# ElectronBoardMKI.net
KiCad netlist of a schematic drawn in EAGLE
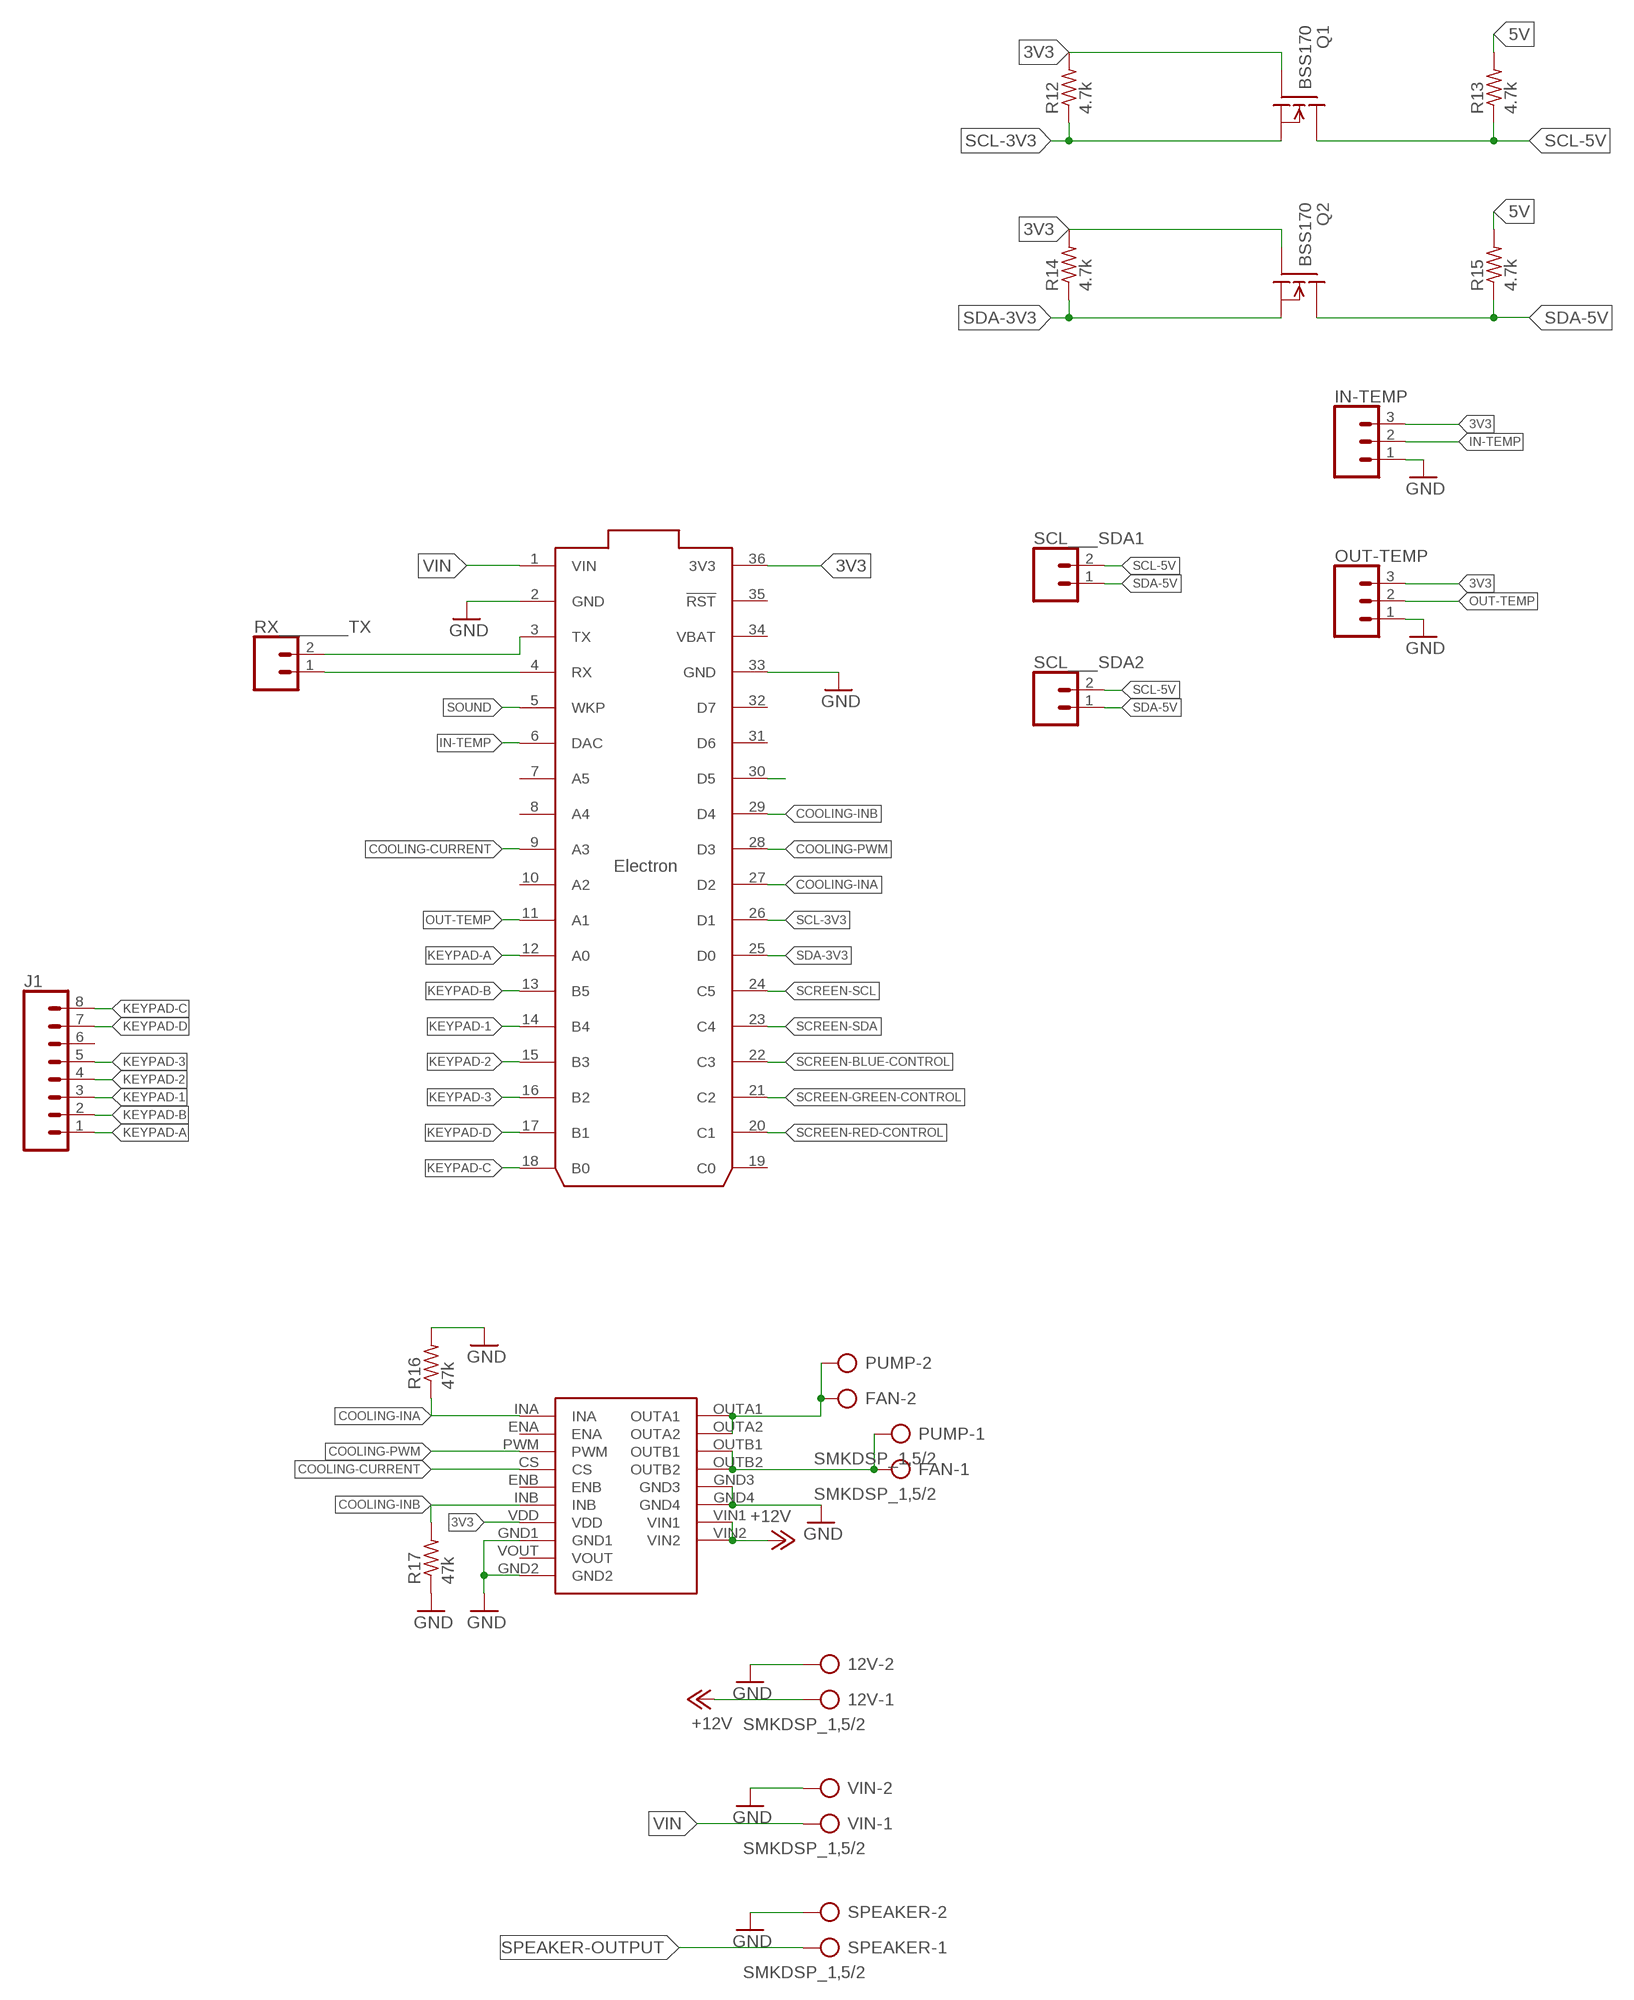
[diagram p0: schematic, sheet 1, part 1 of 2]
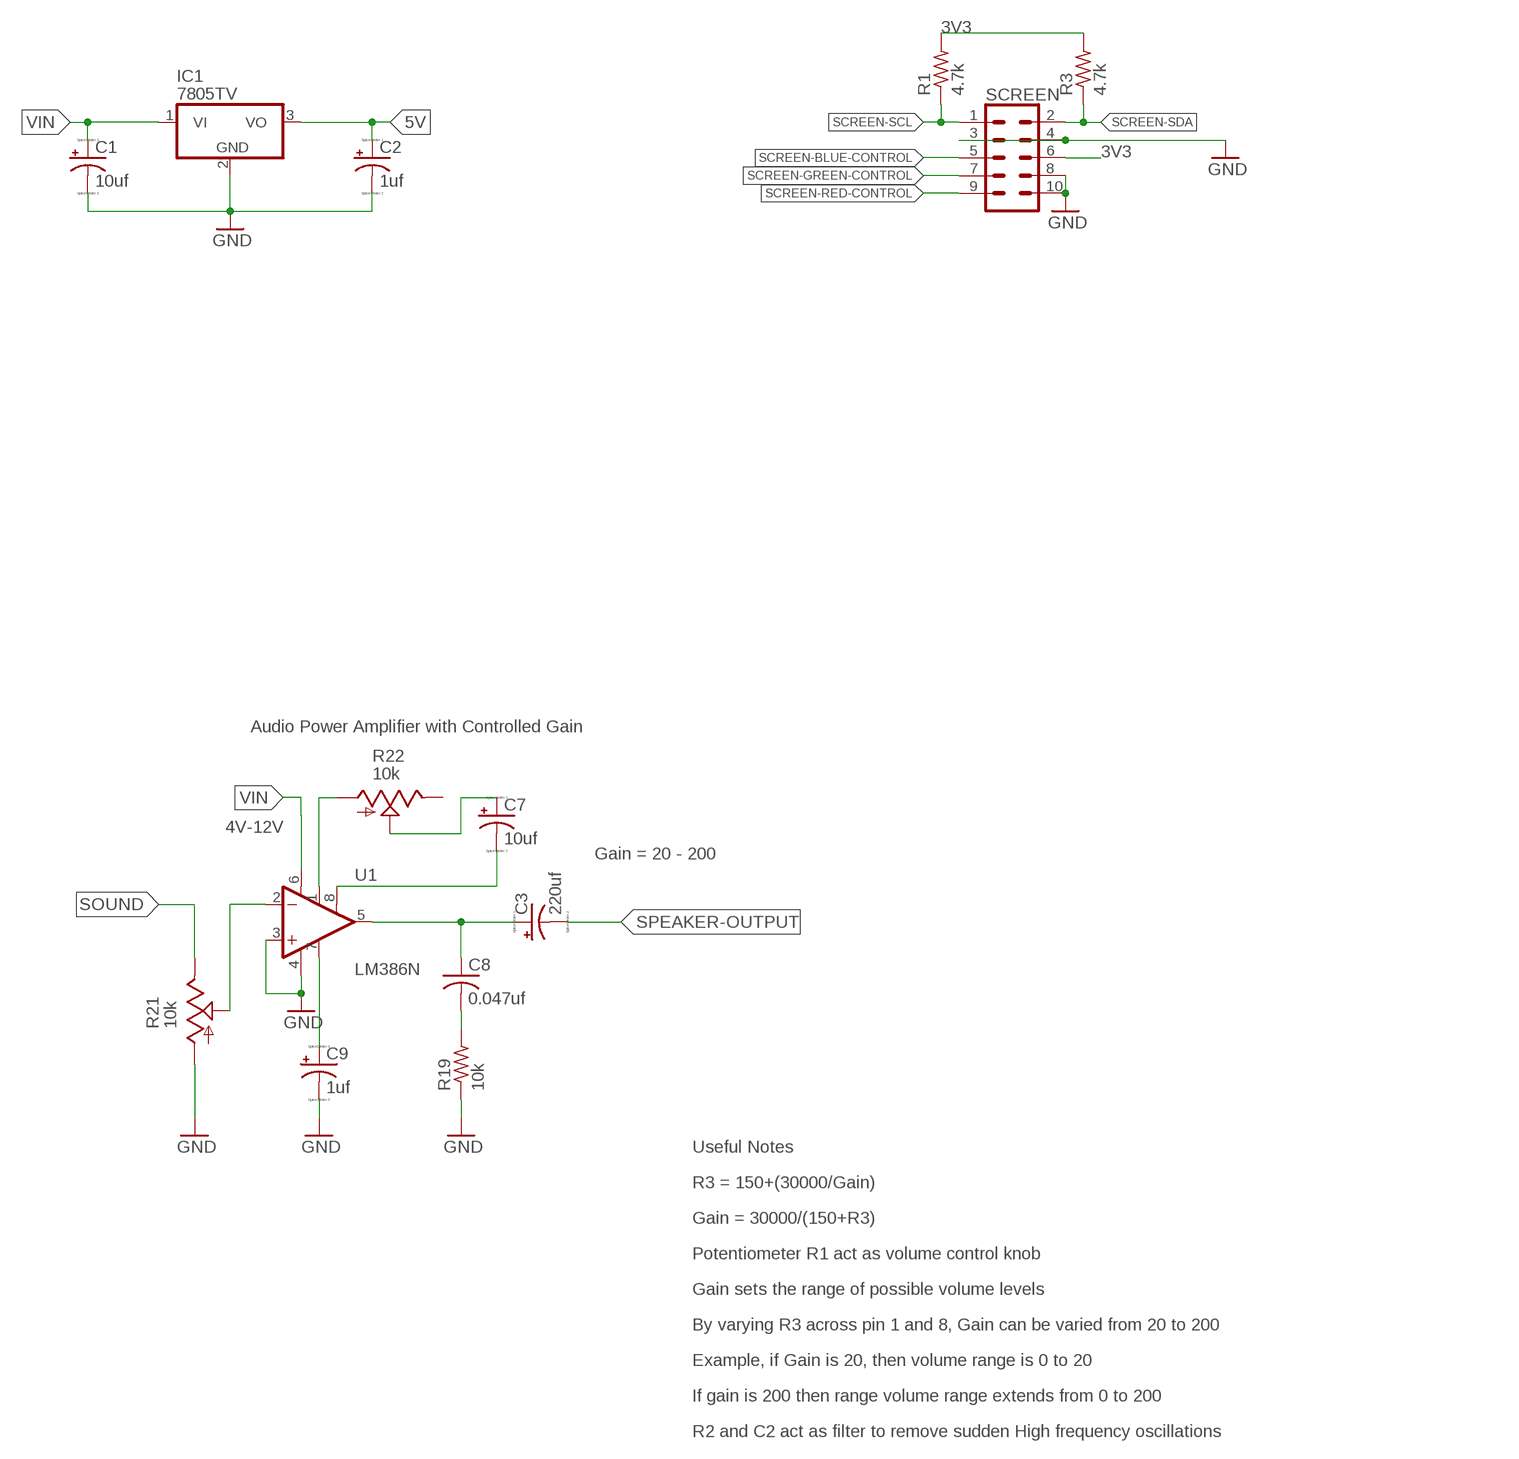
[diagram p1: schematic, sheet 1, part 2 of 2]

(export (version "E")
  (design (tool "Eeschema 10.0.6"))
  (components
    (comp (ref "12V")
      (value "SMKDSP_1,5/2")
      (footprint "eagle-import:SMKDSP_1,5_2")
      (fields (field (name "MF") "FARNELL") (field (name "MPN") "1733570"))
      (libsource (lib "eagle-import") (part "SMKDSP_1,5/2"))
    )
    (comp (ref "C1")
      (value "10uf")
      (footprint "eagle-import:E5-8,5")
      (libsource (lib "eagle-import") (part "CPOL-USE5-8.5"))
    )
    (comp (ref "C2")
      (value "1uf")
      (footprint "eagle-import:E5-8,5")
      (libsource (lib "eagle-import") (part "CPOL-USE5-8.5"))
    )
    (comp (ref "C3")
      (value "220uf")
      (footprint "eagle-import:E5-8,5")
      (libsource (lib "eagle-import") (part "CPOL-USE5-8.5"))
    )
    (comp (ref "C7")
      (value "10uf")
      (footprint "eagle-import:E5-8,5")
      (libsource (lib "eagle-import") (part "CPOL-USE5-8.5"))
    )
    (comp (ref "C8")
      (value "0.047uf")
      (footprint "eagle-import:C050-035X075")
      (libsource (lib "eagle-import") (part "C-US050-035X075"))
    )
    (comp (ref "C9")
      (value "1uf")
      (footprint "eagle-import:E5-8,5")
      (libsource (lib "eagle-import") (part "CPOL-USE5-8.5"))
    )
    (comp (ref "FAN")
      (value "SMKDSP_1,5/2")
      (footprint "eagle-import:SMKDSP_1,5_2")
      (fields (field (name "MF") "FARNELL") (field (name "MPN") "1733570"))
      (libsource (lib "eagle-import") (part "SMKDSP_1,5/2"))
    )
    (comp (ref "IC1")
      (value "7805TV")
      (footprint "eagle-import:TO220V")
      (libsource (lib "eagle-import") (part "78TV05"))
    )
    (comp (ref "IN-TEMP")
      (value "CONN_03LOCK_LONGPADS")
      (footprint "eagle-import:1X03_LOCK_LONGPADS")
      (libsource (lib "eagle-import") (part "CONN_03LOCK_LONGPADS"))
    )
    (comp (ref "J1")
      (value "CONN_08LOCK_LONGPADS")
      (footprint "eagle-import:1X08_LOCK_LONGPADS")
      (libsource (lib "eagle-import") (part "CONN_08LOCK_LONGPADS"))
    )
    (comp (ref "OUT-TEMP")
      (value "CONN_03LOCK_LONGPADS")
      (footprint "eagle-import:1X03_LOCK_LONGPADS")
      (libsource (lib "eagle-import") (part "CONN_03LOCK_LONGPADS"))
    )
    (comp (ref "PUMP")
      (value "SMKDSP_1,5/2")
      (footprint "eagle-import:SMKDSP_1,5_2")
      (fields (field (name "MF") "FARNELL") (field (name "MPN") "1733570"))
      (libsource (lib "eagle-import") (part "SMKDSP_1,5/2"))
    )
    (comp (ref "Q1")
      (value "BSS170")
      (footprint "eagle-import:TO92")
      (libsource (lib "eagle-import") (part "BSS101"))
    )
    (comp (ref "Q2")
      (value "BSS170")
      (footprint "eagle-import:TO92")
      (libsource (lib "eagle-import") (part "BSS101"))
    )
    (comp (ref "R1")
      (value "4.7k")
      (footprint "eagle-import:0207_12")
      (libsource (lib "eagle-import") (part "R-US_0207/12"))
    )
    (comp (ref "R3")
      (value "4.7k")
      (footprint "eagle-import:0207_12")
      (libsource (lib "eagle-import") (part "R-US_0207/12"))
    )
    (comp (ref "R12")
      (value "4.7k")
      (footprint "eagle-import:0207_12")
      (libsource (lib "eagle-import") (part "R-US_0207/12"))
    )
    (comp (ref "R13")
      (value "4.7k")
      (footprint "eagle-import:0207_12")
      (libsource (lib "eagle-import") (part "R-US_0207/12"))
    )
    (comp (ref "R14")
      (value "4.7k")
      (footprint "eagle-import:0207_12")
      (libsource (lib "eagle-import") (part "R-US_0207/12"))
    )
    (comp (ref "R15")
      (value "4.7k")
      (footprint "eagle-import:0207_12")
      (libsource (lib "eagle-import") (part "R-US_0207/12"))
    )
    (comp (ref "R16")
      (value "47k")
      (footprint "eagle-import:0207_12")
      (libsource (lib "eagle-import") (part "R-US_0207/12"))
    )
    (comp (ref "R17")
      (value "47k")
      (footprint "eagle-import:0207_12")
      (libsource (lib "eagle-import") (part "R-US_0207/12"))
    )
    (comp (ref "R19")
      (value "10k")
      (footprint "eagle-import:0207_12")
      (libsource (lib "eagle-import") (part "R-US_0207/12"))
    )
    (comp (ref "R21")
      (value "10k")
      (footprint "eagle-import:CT6")
      (libsource (lib "eagle-import") (part "TRIM_US-CT6"))
    )
    (comp (ref "R22")
      (value "10k")
      (footprint "eagle-import:CT6")
      (libsource (lib "eagle-import") (part "TRIM_US-CT6"))
    )
    (comp (ref "RX_______TX")
      (value "CONN_02LOCK_LONGPADS")
      (footprint "eagle-import:1X02_LOCK_LONGPADS")
      (libsource (lib "eagle-import") (part "CONN_02LOCK_LONGPADS"))
    )
    (comp (ref "SCL___SDA1")
      (value "CONN_02LOCK_LONGPADS")
      (footprint "eagle-import:1X02_LOCK_LONGPADS")
      (libsource (lib "eagle-import") (part "CONN_02LOCK_LONGPADS"))
    )
    (comp (ref "SCL___SDA2")
      (value "CONN_02LOCK_LONGPADS")
      (footprint "eagle-import:1X02_LOCK_LONGPADS")
      (libsource (lib "eagle-import") (part "CONN_02LOCK_LONGPADS"))
    )
    (comp (ref "SCREEN")
      (value "CONN_05X2SHD")
      (footprint "eagle-import:2X5-SHROUDED")
      (libsource (lib "eagle-import") (part "CONN_05X2SHD"))
    )
    (comp (ref "SPEAKER")
      (value "SMKDSP_1,5/2")
      (footprint "eagle-import:SMKDSP_1,5_2")
      (fields (field (name "MF") "FARNELL") (field (name "MPN") "1733570"))
      (libsource (lib "eagle-import") (part "SMKDSP_1,5/2"))
    )
    (comp (ref "U$1")
      (value "ELECTRON_WITH_HEADERS")
      (footprint "eagle-import:ELECTRON")
      (libsource (lib "eagle-import") (part "ELECTRON_WITH_HEADERS"))
    )
    (comp (ref "U$2")
      (value "VNH5019VNH5019BOARD")
      (footprint "eagle-import:DIP3302W60P254L2400H500Q20B")
      (libsource (lib "eagle-import") (part "VNH5019VNH5019BOARD"))
    )
    (comp (ref "U1")
      (value "LM386N")
      (footprint "eagle-import:DIP08")
      (libsource (lib "eagle-import") (part "LM386"))
    )
    (comp (ref "VIN")
      (value "SMKDSP_1,5/2")
      (footprint "eagle-import:SMKDSP_1,5_2")
      (fields (field (name "MF") "FARNELL") (field (name "MPN") "1733570"))
      (libsource (lib "eagle-import") (part "SMKDSP_1,5/2"))
    )
  )
  (nets
    (net (code "1") (name "+12V") (class "Default")
      (node (ref "12V") (pin "1") (pinfunction "KL_1") (pintype "passive"))
      (node (ref "U$2") (pin "VIN1") (pinfunction "VIN1_VIN1") (pintype "bidirectional"))
      (node (ref "U$2") (pin "VIN2") (pinfunction "VIN2_VIN2") (pintype "bidirectional"))
    )
    (net (code "2") (name "/VBAT") (class "Default")
      (node (ref "U$1") (pin "34") (pinfunction "VBAT_34") (pintype "power_in"))
    )
    (net (code "3") (name "3V3") (class "Default")
      (node (ref "IN-TEMP") (pin "3") (pinfunction "3_3") (pintype "passive"))
      (node (ref "OUT-TEMP") (pin "3") (pinfunction "3_3") (pintype "passive"))
      (node (ref "Q1") (pin "2") (pinfunction "G_2") (pintype "passive"))
      (node (ref "Q2") (pin "2") (pinfunction "G_2") (pintype "passive"))
      (node (ref "R1") (pin "2") (pinfunction "2_2") (pintype "passive"))
      (node (ref "R12") (pin "2") (pinfunction "2_2") (pintype "passive"))
      (node (ref "R14") (pin "2") (pinfunction "2_2") (pintype "passive"))
      (node (ref "R3") (pin "2") (pinfunction "2_2") (pintype "passive"))
      (node (ref "SCREEN") (pin "6") (pinfunction "6_6") (pintype "passive"))
      (node (ref "U$1") (pin "36") (pinfunction "3V3_36") (pintype "power_in"))
      (node (ref "U$2") (pin "VDD") (pinfunction "VDD_VDD") (pintype "bidirectional"))
    )
    (net (code "4") (name "5V") (class "Default")
      (node (ref "C2") (pin "+") (pinfunction "+_+") (pintype "passive"))
      (node (ref "IC1") (pin "3") (pinfunction "VO_3") (pintype "passive"))
      (node (ref "R13") (pin "2") (pinfunction "2_2") (pintype "passive"))
      (node (ref "R15") (pin "2") (pinfunction "2_2") (pintype "passive"))
    )
    (net (code "5") (name "COOLING-CURRENT") (class "Default")
      (node (ref "U$1") (pin "9") (pinfunction "A3_9") (pintype "bidirectional"))
      (node (ref "U$2") (pin "CS") (pinfunction "CS_CS") (pintype "bidirectional"))
    )
    (net (code "6") (name "COOLING-INA") (class "Default")
      (node (ref "R16") (pin "1") (pinfunction "1_1") (pintype "passive"))
      (node (ref "U$1") (pin "27") (pinfunction "D2_27") (pintype "bidirectional"))
      (node (ref "U$2") (pin "INA") (pinfunction "INA_INA") (pintype "bidirectional"))
    )
    (net (code "7") (name "COOLING-INB") (class "Default")
      (node (ref "R17") (pin "2") (pinfunction "2_2") (pintype "passive"))
      (node (ref "U$1") (pin "29") (pinfunction "D4_29") (pintype "bidirectional"))
      (node (ref "U$2") (pin "INB") (pinfunction "INB_INB") (pintype "bidirectional"))
    )
    (net (code "8") (name "COOLING-PWM") (class "Default")
      (node (ref "U$1") (pin "28") (pinfunction "D3_28") (pintype "bidirectional"))
      (node (ref "U$2") (pin "PWM") (pinfunction "PWM_PWM") (pintype "bidirectional"))
    )
    (net (code "9") (name "GND") (class "Default")
      (node (ref "12V") (pin "2") (pinfunction "KL_2") (pintype "passive"))
      (node (ref "C1") (pin "-") (pinfunction "-_-") (pintype "passive"))
      (node (ref "C2") (pin "-") (pinfunction "-_-") (pintype "passive"))
      (node (ref "C9") (pin "-") (pinfunction "-_-") (pintype "passive"))
      (node (ref "IC1") (pin "2") (pinfunction "GND_2") (pintype "passive"))
      (node (ref "IN-TEMP") (pin "1") (pinfunction "1_1") (pintype "passive"))
      (node (ref "OUT-TEMP") (pin "1") (pinfunction "1_1") (pintype "passive"))
      (node (ref "R16") (pin "2") (pinfunction "2_2") (pintype "passive"))
      (node (ref "R17") (pin "1") (pinfunction "1_1") (pintype "passive"))
      (node (ref "R19") (pin "1") (pinfunction "1_1") (pintype "passive"))
      (node (ref "R21") (pin "A") (pinfunction "A_A") (pintype "passive"))
      (node (ref "SCREEN") (pin "10") (pinfunction "10_10") (pintype "passive"))
      (node (ref "SCREEN") (pin "3") (pinfunction "3_3") (pintype "passive"))
      (node (ref "SCREEN") (pin "4") (pinfunction "4_4") (pintype "passive"))
      (node (ref "SCREEN") (pin "8") (pinfunction "8_8") (pintype "passive"))
      (node (ref "SPEAKER") (pin "2") (pinfunction "KL_2") (pintype "passive"))
      (node (ref "U$1") (pin "2") (pinfunction "GND_2") (pintype "power_in"))
      (node (ref "U$1") (pin "33") (pinfunction "GND_33") (pintype "power_in"))
      (node (ref "U$2") (pin "GND1") (pinfunction "GND1_GND1") (pintype "bidirectional"))
      (node (ref "U$2") (pin "GND2") (pinfunction "GND2_GND2") (pintype "bidirectional"))
      (node (ref "U$2") (pin "GND3") (pinfunction "GND3_GND3") (pintype "bidirectional"))
      (node (ref "U$2") (pin "GND4") (pinfunction "GND4_GND4") (pintype "bidirectional"))
      (node (ref "U1") (pin "3") (pinfunction "+IN_3") (pintype "input"))
      (node (ref "U1") (pin "4") (pinfunction "V-_4") (pintype "power_in"))
      (node (ref "VIN") (pin "2") (pinfunction "KL_2") (pintype "passive"))
    )
    (net (code "10") (name "IN-TEMP") (class "Default")
      (node (ref "IN-TEMP") (pin "2") (pinfunction "2_2") (pintype "passive"))
      (node (ref "U$1") (pin "6") (pinfunction "DAC_6") (pintype "bidirectional"))
    )
    (net (code "11") (name "KEYPAD-1") (class "Default")
      (node (ref "J1") (pin "3") (pinfunction "3_3") (pintype "passive"))
      (node (ref "U$1") (pin "14") (pinfunction "B4_14") (pintype "bidirectional"))
    )
    (net (code "12") (name "KEYPAD-2") (class "Default")
      (node (ref "J1") (pin "4") (pinfunction "4_4") (pintype "passive"))
      (node (ref "U$1") (pin "15") (pinfunction "B3_15") (pintype "bidirectional"))
    )
    (net (code "13") (name "KEYPAD-3") (class "Default")
      (node (ref "J1") (pin "5") (pinfunction "5_5") (pintype "passive"))
      (node (ref "U$1") (pin "16") (pinfunction "B2_16") (pintype "bidirectional"))
    )
    (net (code "14") (name "KEYPAD-A") (class "Default")
      (node (ref "J1") (pin "1") (pinfunction "1_1") (pintype "passive"))
      (node (ref "U$1") (pin "12") (pinfunction "A0_12") (pintype "bidirectional"))
    )
    (net (code "15") (name "KEYPAD-B") (class "Default")
      (node (ref "J1") (pin "2") (pinfunction "2_2") (pintype "passive"))
      (node (ref "U$1") (pin "13") (pinfunction "B5_13") (pintype "bidirectional"))
    )
    (net (code "16") (name "KEYPAD-C") (class "Default")
      (node (ref "J1") (pin "8") (pinfunction "8_8") (pintype "passive"))
      (node (ref "U$1") (pin "18") (pinfunction "B0_18") (pintype "bidirectional"))
    )
    (net (code "17") (name "KEYPAD-D") (class "Default")
      (node (ref "J1") (pin "7") (pinfunction "7_7") (pintype "passive"))
      (node (ref "U$1") (pin "17") (pinfunction "B1_17") (pintype "bidirectional"))
    )
    (net (code "18") (name "Net-(C7-Pad+)") (class "Default")
      (node (ref "C7") (pin "+") (pinfunction "+_+") (pintype "passive"))
      (node (ref "R22") (pin "S") (pinfunction "S_S") (pintype "passive"))
    )
    (net (code "19") (name "Net-(C7-Pad-)") (class "Default")
      (node (ref "C7") (pin "-") (pinfunction "-_-") (pintype "passive"))
      (node (ref "U1") (pin "8") (pinfunction "GAIN_8") (pintype "bidirectional"))
    )
    (net (code "20") (name "Net-(C8-Pad2)") (class "Default")
      (node (ref "C8") (pin "2") (pinfunction "2_2") (pintype "passive"))
      (node (ref "R19") (pin "2") (pinfunction "2_2") (pintype "passive"))
    )
    (net (code "21") (name "Net-(FANA-KL)") (class "Default")
      (node (ref "FAN") (pin "1") (pinfunction "KL_1") (pintype "passive"))
      (node (ref "PUMP") (pin "1") (pinfunction "KL_1") (pintype "passive"))
      (node (ref "U$2") (pin "OUTB1") (pinfunction "OUTB1_OUTB1") (pintype "bidirectional"))
      (node (ref "U$2") (pin "OUTB2") (pinfunction "OUTB2_OUTB2") (pintype "bidirectional"))
    )
    (net (code "22") (name "Net-(FANB-KL)") (class "Default")
      (node (ref "FAN") (pin "2") (pinfunction "KL_2") (pintype "passive"))
      (node (ref "PUMP") (pin "2") (pinfunction "KL_2") (pintype "passive"))
      (node (ref "U$2") (pin "OUTA1") (pinfunction "OUTA1_OUTA1") (pintype "bidirectional"))
      (node (ref "U$2") (pin "OUTA2") (pinfunction "OUTA2_OUTA2") (pintype "bidirectional"))
    )
    (net (code "23") (name "Net-(R22-PadA)") (class "Default")
      (node (ref "R22") (pin "A") (pinfunction "A_A") (pintype "passive"))
      (node (ref "U1") (pin "1") (pinfunction "GAIN_1") (pintype "bidirectional"))
    )
    (net (code "24") (name "Net-(U$1-RX)") (class "Default")
      (node (ref "RX_______TX") (pin "1") (pinfunction "1_1") (pintype "passive"))
      (node (ref "U$1") (pin "4") (pinfunction "RX_4") (pintype "bidirectional"))
    )
    (net (code "25") (name "Net-(U$1-TX)") (class "Default")
      (node (ref "RX_______TX") (pin "2") (pinfunction "2_2") (pintype "passive"))
      (node (ref "U$1") (pin "3") (pinfunction "TX_3") (pintype "bidirectional"))
    )
    (net (code "26") (name "Net-(U1--IN)") (class "Default")
      (node (ref "R21") (pin "S") (pinfunction "S_S") (pintype "passive"))
      (node (ref "U1") (pin "2") (pinfunction "-IN_2") (pintype "input"))
    )
    (net (code "27") (name "Net-(U1-BP)") (class "Default")
      (node (ref "C9") (pin "+") (pinfunction "+_+") (pintype "passive"))
      (node (ref "U1") (pin "7") (pinfunction "BP_7") (pintype "bidirectional"))
    )
    (net (code "28") (name "Net-(U1-OUT)") (class "Default")
      (node (ref "C3") (pin "+") (pinfunction "+_+") (pintype "passive"))
      (node (ref "C8") (pin "1") (pinfunction "1_1") (pintype "passive"))
      (node (ref "U1") (pin "5") (pinfunction "OUT_5") (pintype "output"))
    )
    (net (code "29") (name "OUT-TEMP") (class "Default")
      (node (ref "OUT-TEMP") (pin "2") (pinfunction "2_2") (pintype "passive"))
      (node (ref "U$1") (pin "11") (pinfunction "A1_11") (pintype "bidirectional"))
    )
    (net (code "30") (name "SCL-3V3") (class "Default")
      (node (ref "Q1") (pin "1") (pinfunction "S_1") (pintype "passive"))
      (node (ref "R12") (pin "1") (pinfunction "1_1") (pintype "passive"))
      (node (ref "U$1") (pin "26") (pinfunction "D1_26") (pintype "bidirectional"))
    )
    (net (code "31") (name "SCL-5V") (class "Default")
      (node (ref "Q1") (pin "3") (pinfunction "D_3") (pintype "passive"))
      (node (ref "R13") (pin "1") (pinfunction "1_1") (pintype "passive"))
      (node (ref "SCL___SDA1") (pin "2") (pinfunction "2_2") (pintype "passive"))
      (node (ref "SCL___SDA2") (pin "2") (pinfunction "2_2") (pintype "passive"))
    )
    (net (code "32") (name "SCREEN-BLUE-CONTROL") (class "Default")
      (node (ref "SCREEN") (pin "5") (pinfunction "5_5") (pintype "passive"))
      (node (ref "U$1") (pin "22") (pinfunction "C3_22") (pintype "bidirectional"))
    )
    (net (code "33") (name "SCREEN-GREEN-CONTROL") (class "Default")
      (node (ref "SCREEN") (pin "7") (pinfunction "7_7") (pintype "passive"))
      (node (ref "U$1") (pin "21") (pinfunction "C2_21") (pintype "bidirectional"))
    )
    (net (code "34") (name "SCREEN-RED-CONTROL") (class "Default")
      (node (ref "SCREEN") (pin "9") (pinfunction "9_9") (pintype "passive"))
      (node (ref "U$1") (pin "20") (pinfunction "C1_20") (pintype "bidirectional"))
    )
    (net (code "35") (name "SCREEN-SCL") (class "Default")
      (node (ref "R1") (pin "1") (pinfunction "1_1") (pintype "passive"))
      (node (ref "SCREEN") (pin "1") (pinfunction "1_1") (pintype "passive"))
      (node (ref "U$1") (pin "24") (pinfunction "C5_24") (pintype "bidirectional"))
    )
    (net (code "36") (name "SCREEN-SDA") (class "Default")
      (node (ref "R3") (pin "1") (pinfunction "1_1") (pintype "passive"))
      (node (ref "SCREEN") (pin "2") (pinfunction "2_2") (pintype "passive"))
      (node (ref "U$1") (pin "23") (pinfunction "C4_23") (pintype "bidirectional"))
    )
    (net (code "37") (name "SDA-3V3") (class "Default")
      (node (ref "Q2") (pin "1") (pinfunction "S_1") (pintype "passive"))
      (node (ref "R14") (pin "1") (pinfunction "1_1") (pintype "passive"))
      (node (ref "U$1") (pin "25") (pinfunction "D0_25") (pintype "bidirectional"))
    )
    (net (code "38") (name "SDA-5V") (class "Default")
      (node (ref "Q2") (pin "3") (pinfunction "D_3") (pintype "passive"))
      (node (ref "R15") (pin "1") (pinfunction "1_1") (pintype "passive"))
      (node (ref "SCL___SDA1") (pin "1") (pinfunction "1_1") (pintype "passive"))
      (node (ref "SCL___SDA2") (pin "1") (pinfunction "1_1") (pintype "passive"))
    )
    (net (code "39") (name "SOUND") (class "Default")
      (node (ref "R21") (pin "E") (pinfunction "E_E") (pintype "passive"))
      (node (ref "U$1") (pin "5") (pinfunction "WKP_5") (pintype "bidirectional"))
    )
    (net (code "40") (name "SPEAKER-OUTPUT") (class "Default")
      (node (ref "C3") (pin "-") (pinfunction "-_-") (pintype "passive"))
      (node (ref "SPEAKER") (pin "1") (pinfunction "KL_1") (pintype "passive"))
    )
    (net (code "41") (name "VIN") (class "Default")
      (node (ref "C1") (pin "+") (pinfunction "+_+") (pintype "passive"))
      (node (ref "IC1") (pin "1") (pinfunction "VI_1") (pintype "input"))
      (node (ref "U$1") (pin "1") (pinfunction "VIN_1") (pintype "power_in"))
      (node (ref "U1") (pin "6") (pinfunction "V+_6") (pintype "power_in"))
      (node (ref "VIN") (pin "1") (pinfunction "KL_1") (pintype "passive"))
    )
    (net (code "42") (name "unconnected-(J1-Pad6)") (class "Default")
      (node (ref "J1") (pin "6") (pinfunction "6_6") (pintype "passive"))
    )
    (net (code "43") (name "unconnected-(R22-PadE)") (class "Default")
      (node (ref "R22") (pin "E") (pinfunction "E_E") (pintype "passive"))
    )
    (net (code "44") (name "unconnected-(U$1-A2-Pad10)") (class "Default")
      (node (ref "U$1") (pin "10") (pinfunction "A2_10") (pintype "bidirectional"))
    )
    (net (code "45") (name "unconnected-(U$1-A4-Pad8)") (class "Default")
      (node (ref "U$1") (pin "8") (pinfunction "A4_8") (pintype "bidirectional"))
    )
    (net (code "46") (name "unconnected-(U$1-A5-Pad7)") (class "Default")
      (node (ref "U$1") (pin "7") (pinfunction "A5_7") (pintype "bidirectional"))
    )
    (net (code "47") (name "unconnected-(U$1-C0-Pad19)") (class "Default")
      (node (ref "U$1") (pin "19") (pinfunction "C0_19") (pintype "bidirectional"))
    )
    (net (code "48") (name "unconnected-(U$1-D5-Pad30)") (class "Default")
      (node (ref "U$1") (pin "30") (pinfunction "D5_30") (pintype "bidirectional"))
    )
    (net (code "49") (name "unconnected-(U$1-D6-Pad31)") (class "Default")
      (node (ref "U$1") (pin "31") (pinfunction "D6_31") (pintype "bidirectional"))
    )
    (net (code "50") (name "unconnected-(U$1-D7-Pad32)") (class "Default")
      (node (ref "U$1") (pin "32") (pinfunction "D7_32") (pintype "bidirectional"))
    )
    (net (code "51") (name "unconnected-(U$1-~{RST}-Pad35)") (class "Default")
      (node (ref "U$1") (pin "35") (pinfunction "~{RST}_35") (pintype "bidirectional"))
    )
    (net (code "52") (name "unconnected-(U$2-PadENA)") (class "Default")
      (node (ref "U$2") (pin "ENA") (pinfunction "ENA_ENA") (pintype "bidirectional"))
    )
    (net (code "53") (name "unconnected-(U$2-PadENB)") (class "Default")
      (node (ref "U$2") (pin "ENB") (pinfunction "ENB_ENB") (pintype "bidirectional"))
    )
    (net (code "54") (name "unconnected-(U$2-PadVOUT)") (class "Default")
      (node (ref "U$2") (pin "VOUT") (pinfunction "VOUT_VOUT") (pintype "bidirectional"))
    )
  )
)
